# 4_mcu.net
KiCad netlist of a schematic drawn in Altium Designer
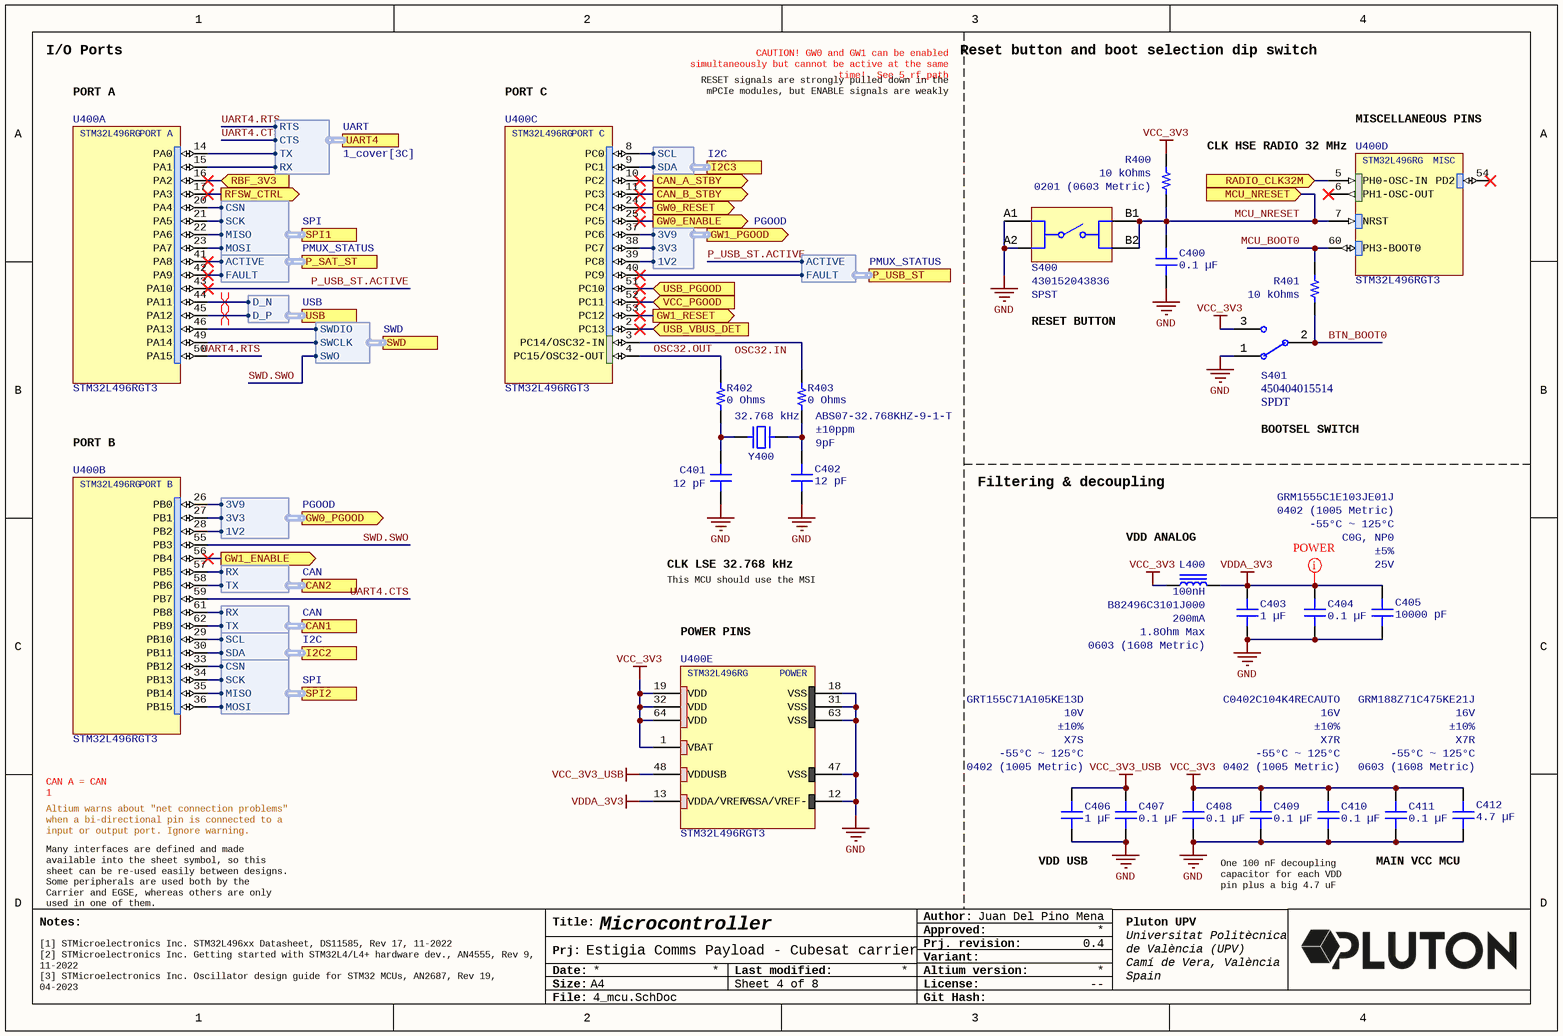
[diagram p0: 4_mcu.SchDoc]

(export (version "E")
  (design (tool "Eeschema 10.0.6"))
  (components
    (comp (ref "C400")
      (value "0.1 µF")
      (footprint "CAP 0402_1005")
      (description "CAP CER 0402 0.1UF 16V X7R 10%")
      (fields (field (name "PART NUMBER") "C0402C104K4RECAUTO") (field (name "MANUFACTURER") "KEMET"))
      (libsource (lib "Celestial Altium Library - altium_library") (part "Capacitor"))
    )
    (comp (ref "C401")
      (value "12 pF")
      (footprint "CAP 0201_0603")
      (description "CAP CER 12PF 25V C0G/NP0 0201")
      (fields (field (name "PART NUMBER") "CBR02C120F3GAC") (field (name "MANUFACTURER") "KEMET"))
      (libsource (lib "Celestial Altium Library - altium_library") (part "Capacitor"))
    )
    (comp (ref "C402")
      (value "12 pF")
      (footprint "CAP 0201_0603")
      (description "CAP CER 12PF 25V C0G/NP0 0201")
      (fields (field (name "PART NUMBER") "CBR02C120F3GAC") (field (name "MANUFACTURER") "KEMET"))
      (libsource (lib "Celestial Altium Library - altium_library") (part "Capacitor"))
    )
    (comp (ref "C403")
      (value "1 µF")
      (footprint "CAP 0402_1005")
      (description "CAP CER 1UF 10V X7S 0402")
      (fields
        (field (name "PART NUMBER") "GRT155C71A105KE13D")
        (field (name "MANUFACTURER") "Murata Electronics")
      )
      (libsource (lib "Celestial Altium Library - altium_library") (part "Capacitor"))
    )
    (comp (ref "C404")
      (value "0.1 µF")
      (footprint "CAP 0402_1005")
      (description "CAP CER 0402 0.1UF 16V X7R 10%")
      (fields (field (name "PART NUMBER") "C0402C104K4RECAUTO") (field (name "MANUFACTURER") "KEMET"))
      (libsource (lib "Celestial Altium Library - altium_library") (part "Capacitor"))
    )
    (comp (ref "C405")
      (value "10000 pF")
      (footprint "CAP 0402_1005")
      (description "CAP CER 10000PF 25V C0G/NP0 0402")
      (fields
        (field (name "PART NUMBER") "GRM1555C1E103JE01J")
        (field (name "DEVICE PACKAGE") "0402 (1005 Metric)")
        (field (name "MANUFACTURER") "Murata Electronics")
        (field (name "OPERATING TEMPERATURE") "-55°C ~ 125°C")
        (field (name "TEMPERATURE COEFFICIENT") "C0G, NP0")
        (field (name "TOLERANCE") "±5%")
        (field (name "VOLTAGE - RATED") "25V")
      )
      (libsource (lib "Celestial Altium Library - altium_library") (part "Capacitor"))
    )
    (comp (ref "C406")
      (value "1 µF")
      (footprint "CAP 0402_1005")
      (description "CAP CER 1UF 10V X7S 0402")
      (fields
        (field (name "PART NUMBER") "GRT155C71A105KE13D")
        (field (name "DEVICE PACKAGE") "0402 (1005 Metric)")
        (field (name "MANUFACTURER") "Murata Electronics")
        (field (name "OPERATING TEMPERATURE") "-55°C ~ 125°C")
        (field (name "TEMPERATURE COEFFICIENT") "X7S")
        (field (name "TOLERANCE") "±10%")
        (field (name "VOLTAGE - RATED") "10V")
      )
      (libsource (lib "Celestial Altium Library - altium_library") (part "Capacitor"))
    )
    (comp (ref "C407")
      (value "0.1 µF")
      (footprint "CAP 0402_1005")
      (description "CAP CER 0402 0.1UF 16V X7R 10%")
      (fields (field (name "PART NUMBER") "C0402C104K4RECAUTO") (field (name "MANUFACTURER") "KEMET"))
      (libsource (lib "Celestial Altium Library - altium_library") (part "Capacitor"))
    )
    (comp (ref "C408")
      (value "0.1 µF")
      (footprint "CAP 0402_1005")
      (description "CAP CER 0402 0.1UF 16V X7R 10%")
      (fields (field (name "PART NUMBER") "C0402C104K4RECAUTO") (field (name "MANUFACTURER") "KEMET"))
      (libsource (lib "Celestial Altium Library - altium_library") (part "Capacitor"))
    )
    (comp (ref "C409")
      (value "0.1 µF")
      (footprint "CAP 0402_1005")
      (description "CAP CER 0402 0.1UF 16V X7R 10%")
      (fields
        (field (name "PART NUMBER") "C0402C104K4RECAUTO")
        (field (name "MANUFACTURER") "KEMET")
        (field (name "OPERATING TEMPERATURE") "-55°C ~ 125°C")
        (field (name "PACKAGE / CASE") "0402 (1005 Metric)")
        (field (name "TEMPERATURE COEFFICIENT") "X7R")
        (field (name "TOLERANCE") "±10%")
        (field (name "VOLTAGE - RATED") "16V")
      )
      (libsource (lib "Celestial Altium Library - altium_library") (part "Capacitor"))
    )
    (comp (ref "C410")
      (value "0.1 µF")
      (footprint "CAP 0402_1005")
      (description "CAP CER 0402 0.1UF 16V X7R 10%")
      (fields (field (name "PART NUMBER") "C0402C104K4RECAUTO") (field (name "MANUFACTURER") "KEMET"))
      (libsource (lib "Celestial Altium Library - altium_library") (part "Capacitor"))
    )
    (comp (ref "C411")
      (value "0.1 µF")
      (footprint "CAP 0402_1005")
      (description "CAP CER 0402 0.1UF 16V X7R 10%")
      (fields (field (name "PART NUMBER") "C0402C104K4RECAUTO") (field (name "MANUFACTURER") "KEMET"))
      (libsource (lib "Celestial Altium Library - altium_library") (part "Capacitor"))
    )
    (comp (ref "C412")
      (value "4.7 µF")
      (footprint "CAP 0603_1608")
      (description "CAP CER 4.7UF 16V X7R 0603")
      (fields
        (field (name "PART NUMBER") "GRM188Z71C475KE21J")
        (field (name "DEVICE PACKAGE") "0603 (1608 Metric)")
        (field (name "MANUFACTURER") "Murata Electronics")
        (field (name "OPERATING TEMPERATURE") "-55°C ~ 125°C")
        (field (name "TEMPERATURE COEFFICIENT") "X7R")
        (field (name "TOLERANCE") "±10%")
        (field (name "VOLTAGE - RATED") "16V")
      )
      (libsource (lib "Celestial Altium Library - altium_library") (part "Capacitor"))
    )
    (comp (ref "L400")
      (value "100nH")
      (footprint "IND 0603_1608 RF WW")
      (description "FIXED IND 100NH 200MA 1.8 OHM")
      (fields
        (field (name "PART NUMBER") "B82496C3101J000")
        (field (name "CURRENT RATING (AMPS)") "200mA")
        (field (name "DC RESISTANCE (DCR)") "1.8Ohm Max")
        (field (name "DEVICE PACKAGE") "0603 (1608 Metric)")
        (field (name "MANUFACTURER") "TDK Electronics Inc.")
        (field (name "TOLERANCE") "±5%")
      )
      (libsource (lib "Celestial Altium Library - altium_library") (part "Inductor"))
    )
    (comp (ref "R400")
      (value "10 kOhms")
      (footprint "RES 0201_0603")
      (description "RES SMD 10K OHM 1% 1/20W 0201")
      (fields
        (field (name "PART NUMBER") "AF0201FR-0710KL")
        (field (name "MANUFACTURER") "Yageo")
        (field (name "PACKAGE / CASE") "0201 (0603 Metric)")
      )
      (libsource (lib "Celestial Altium Library - altium_library") (part "Resistor"))
    )
    (comp (ref "R401")
      (value "10 kOhms")
      (footprint "RES 0201_0603")
      (description "RES SMD 10K OHM 1% 1/20W 0201")
      (fields (field (name "PART NUMBER") "AF0201FR-0710KL") (field (name "MANUFACTURER") "Yageo"))
      (libsource (lib "Celestial Altium Library - altium_library") (part "Resistor"))
    )
    (comp (ref "R402")
      (value "0 Ohms")
      (footprint "RES 0201_0603")
      (description "RES SMD 0 OHM JUMPER 1/20W 0201")
      (fields (field (name "PART NUMBER") "AC0201JR-070RL") (field (name "MANUFACTURER") "Yageo"))
      (libsource (lib "Celestial Altium Library - altium_library") (part "Resistor"))
    )
    (comp (ref "R403")
      (value "0 Ohms")
      (footprint "RES 0201_0603")
      (description "RES SMD 0 OHM JUMPER 1/20W 0201")
      (fields (field (name "PART NUMBER") "AC0201JR-070RL") (field (name "MANUFACTURER") "Yageo"))
      (libsource (lib "Celestial Altium Library - altium_library") (part "Resistor"))
    )
    (comp (ref "S400")
      (value "430152043836")
      (footprint "WS-TASV_L6W6H4.3_4301x20438x6")
      (fields (field (name "THROW CONFIGURATION") "SPST"))
      (libsource (lib "Altium Content Vault") (part "SPST-NO_4P"))
    )
    (comp (ref "S401")
      (value "450404015514")
      (footprint "WURTH WS-SLSU 450404015514")
      (description "MINI SLIDE SWITCH 6.7 X 2.7 MM.")
      (fields
        (field (name "PART NUMBER") "450404015514")
        (field (name "CIRCUIT") "SPDT")
        (field (name "MANUFACTURER") "Würth Elektronik")
        (field (name "PUBLISHER") "Wurth Elektronik")
      )
      (libsource (lib "Celestial Altium Library - altium_library") (part "WURTH WS-SLSU 450404015514"))
    )
    (comp (ref "U400")
      (value "STM32L496RGT3")
      (footprint "ics:LQFP64")
      (libsource (lib "stm32") (part "STM32L496RGT3"))
    )
    (comp (ref "Y400")
      (value "32.768 kHz")
      (footprint "ABRACON ABS07")
      (description "CRYSTAL 32.7680KHZ 9PF SMD")
      (fields
        (field (name "PART NUMBER") "ABS07-32.768KHZ-9-1-T")
        (field (name "FREQUENCY") "32.768 kHz")
        (field (name "FREQUENCY TOLERANCE") "±10ppm")
        (field (name "LOAD CAPACITANCE") "9pF")
        (field (name "MANUFACTURER") "Abracon LLC")
      )
      (libsource (lib "Celestial Altium Library - altium_library") (part "Abracon Crystal ABS07"))
    )
  )
  (nets
    (net (code "9") (name "/BTN_BOOT0") (class "Default")
      (node (ref "R401") (pin "1") (pinfunction "1_1") (pintype "passive"))
      (node (ref "S401") (pin "2") (pinfunction "COM_2") (pintype "passive"))
    )
    (net (code "10") (name "/CAN_A_STBY") (class "Default")
      (node (ref "U400") (pin "10") (pinfunction "PC2_10") (pintype "bidirectional+no_connect"))
    )
    (net (code "11") (name "/CAN_B_STBY") (class "Default")
      (node (ref "U400") (pin "11") (pinfunction "PC3_11") (pintype "bidirectional+no_connect"))
    )
    (net (code "12") (name "/D_N") (class "Default")
      (node (ref "U400") (pin "44") (pinfunction "PA11_44") (pintype "bidirectional"))
    )
    (net (code "13") (name "/D_P") (class "Default")
      (node (ref "U400") (pin "45") (pinfunction "PA12_45") (pintype "bidirectional"))
    )
    (net (code "14") (name "/GW0_ENABLE") (class "Default")
      (node (ref "U400") (pin "25") (pinfunction "PC5_25") (pintype "bidirectional+no_connect"))
    )
    (net (code "15") (name "/GW0_RESET") (class "Default")
      (node (ref "U400") (pin "24") (pinfunction "PC4_24") (pintype "bidirectional+no_connect"))
    )
    (net (code "16") (name "/GW1_ENABLE") (class "Default")
      (node (ref "U400") (pin "56") (pinfunction "PB4_56") (pintype "bidirectional+no_connect"))
    )
    (net (code "17") (name "/GW1_RESET") (class "Default")
      (node (ref "U400") (pin "53") (pinfunction "PC12_53") (pintype "bidirectional+no_connect"))
    )
    (net (code "19") (name "/MCU_BOOT0") (class "Default")
      (node (ref "R401") (pin "2") (pinfunction "2_2") (pintype "passive"))
      (node (ref "U400") (pin "60") (pinfunction "PH3-BOOT0_60") (pintype "bidirectional"))
    )
    (net (code "20") (name "/MCU_NRESET") (class "Default")
      (node (ref "C400") (pin "2") (pinfunction "2_2") (pintype "passive"))
      (node (ref "R400") (pin "1") (pinfunction "1_1") (pintype "passive"))
      (node (ref "S400") (pin "B1") (pinfunction "B1_B1") (pintype "passive"))
      (node (ref "S400") (pin "B2") (pinfunction "B2_B2") (pintype "passive"))
      (node (ref "U400") (pin "7") (pinfunction "NRST_7") (pintype "input"))
    )
    (net (code "21") (name "/OSC32.IN") (class "Default")
      (node (ref "R403") (pin "2") (pinfunction "2_2") (pintype "passive"))
      (node (ref "U400") (pin "3") (pinfunction "PC14/OSC32-IN_3") (pintype "bidirectional"))
    )
    (net (code "22") (name "/OSC32.OUT") (class "Default")
      (node (ref "R402") (pin "2") (pinfunction "2_2") (pintype "passive"))
      (node (ref "U400") (pin "4") (pinfunction "PC15/OSC32-OUT_4") (pintype "bidirectional"))
    )
    (net (code "23") (name "/P_USB_ST.ACTIVE") (class "Default")
      (node (ref "U400") (pin "43") (pinfunction "PA10_43") (pintype "bidirectional+no_connect"))
    )
    (net (code "24") (name "/RADIO_CLK32M") (class "Default")
      (node (ref "U400") (pin "5") (pinfunction "PH0-OSC-IN_5") (pintype "input"))
    )
    (net (code "25") (name "/RBF_3V3") (class "Default")
      (node (ref "U400") (pin "16") (pinfunction "PA2_16") (pintype "bidirectional+no_connect"))
    )
    (net (code "26") (name "/RFSW_CTRL") (class "Default")
      (node (ref "U400") (pin "17") (pinfunction "PA3_17") (pintype "bidirectional+no_connect"))
    )
    (net (code "27") (name "/SWCLK") (class "Default")
      (node (ref "U400") (pin "49") (pinfunction "PA14_49") (pintype "bidirectional"))
    )
    (net (code "28") (name "/SWD.SWO") (class "Default")
      (node (ref "U400") (pin "55") (pinfunction "PB3_55") (pintype "bidirectional"))
    )
    (net (code "29") (name "/SWDIO") (class "Default")
      (node (ref "U400") (pin "46") (pinfunction "PA13_46") (pintype "bidirectional"))
    )
    (net (code "30") (name "/UART4.CTS") (class "Default")
      (node (ref "U400") (pin "59") (pinfunction "PB7_59") (pintype "bidirectional"))
    )
    (net (code "31") (name "/UART4.RTS") (class "Default")
      (node (ref "U400") (pin "50") (pinfunction "PA15_50") (pintype "bidirectional"))
    )
    (net (code "32") (name "/USB_PGOOD") (class "Default")
      (node (ref "U400") (pin "51") (pinfunction "PC10_51") (pintype "bidirectional+no_connect"))
    )
    (net (code "33") (name "/USB_VBUS_DET") (class "Default")
      (node (ref "U400") (pin "2") (pinfunction "PC13_2") (pintype "bidirectional+no_connect"))
    )
    (net (code "34") (name "/VCC_PGOOD") (class "Default")
      (node (ref "U400") (pin "52") (pinfunction "PC11_52") (pintype "bidirectional+no_connect"))
    )
    (net (code "42") (name "GND") (class "Default")
      (node (ref "C400") (pin "1") (pinfunction "1_1") (pintype "passive"))
      (node (ref "C401") (pin "1") (pinfunction "1_1") (pintype "passive"))
      (node (ref "C402") (pin "1") (pinfunction "1_1") (pintype "passive"))
      (node (ref "C403") (pin "1") (pinfunction "1_1") (pintype "passive"))
      (node (ref "C404") (pin "1") (pinfunction "1_1") (pintype "passive"))
      (node (ref "C405") (pin "1") (pinfunction "1_1") (pintype "passive"))
      (node (ref "C406") (pin "1") (pinfunction "1_1") (pintype "passive"))
      (node (ref "C407") (pin "1") (pinfunction "1_1") (pintype "passive"))
      (node (ref "C408") (pin "1") (pinfunction "1_1") (pintype "passive"))
      (node (ref "C409") (pin "1") (pinfunction "1_1") (pintype "passive"))
      (node (ref "C410") (pin "1") (pinfunction "1_1") (pintype "passive"))
      (node (ref "C411") (pin "1") (pinfunction "1_1") (pintype "passive"))
      (node (ref "C412") (pin "1") (pinfunction "1_1") (pintype "passive"))
      (node (ref "S400") (pin "A1") (pinfunction "A1_A1") (pintype "passive"))
      (node (ref "S400") (pin "A2") (pinfunction "A2_A2") (pintype "passive"))
      (node (ref "S401") (pin "1") (pinfunction "1_1") (pintype "passive"))
      (node (ref "U400") (pin "12") (pinfunction "VSSA/VREF-_12") (pintype "power_in"))
      (node (ref "U400") (pin "18") (pinfunction "VSS_18") (pintype "power_in"))
      (node (ref "U400") (pin "31") (pinfunction "VSS_31") (pintype "power_in"))
      (node (ref "U400") (pin "47") (pinfunction "VSS_47") (pintype "power_in"))
      (node (ref "U400") (pin "63") (pinfunction "VSS_63") (pintype "power_in"))
    )
    (net (code "43") (name "Net-(C401-Pad2)") (class "Default")
      (node (ref "C401") (pin "2") (pinfunction "2_2") (pintype "passive"))
      (node (ref "R402") (pin "1") (pinfunction "1_1") (pintype "passive"))
      (node (ref "Y400") (pin "1") (pinfunction "1_1") (pintype "passive"))
    )
    (net (code "44") (name "Net-(C402-Pad2)") (class "Default")
      (node (ref "C402") (pin "2") (pinfunction "2_2") (pintype "passive"))
      (node (ref "R403") (pin "1") (pinfunction "1_1") (pintype "passive"))
      (node (ref "Y400") (pin "2") (pinfunction "2_2") (pintype "passive"))
    )
    (net (code "45") (name "VCC_3V3") (class "Default")
      (node (ref "C408") (pin "2") (pinfunction "2_2") (pintype "passive"))
      (node (ref "C409") (pin "2") (pinfunction "2_2") (pintype "passive"))
      (node (ref "C410") (pin "2") (pinfunction "2_2") (pintype "passive"))
      (node (ref "C411") (pin "2") (pinfunction "2_2") (pintype "passive"))
      (node (ref "C412") (pin "2") (pinfunction "2_2") (pintype "passive"))
      (node (ref "L400") (pin "1") (pinfunction "1_1") (pintype "passive"))
      (node (ref "R400") (pin "2") (pinfunction "2_2") (pintype "passive"))
      (node (ref "S401") (pin "3") (pinfunction "3_3") (pintype "passive"))
      (node (ref "U400") (pin "1") (pinfunction "VBAT_1") (pintype "power_in"))
      (node (ref "U400") (pin "19") (pinfunction "VDD_19") (pintype "power_in"))
      (node (ref "U400") (pin "32") (pinfunction "VDD_32") (pintype "power_in"))
      (node (ref "U400") (pin "64") (pinfunction "VDD_64") (pintype "power_in"))
    )
    (net (code "46") (name "VCC_3V3_USB") (class "Default")
      (node (ref "C406") (pin "2") (pinfunction "2_2") (pintype "passive"))
      (node (ref "C407") (pin "2") (pinfunction "2_2") (pintype "passive"))
      (node (ref "U400") (pin "48") (pinfunction "VDDUSB_48") (pintype "power_in"))
    )
    (net (code "47") (name "VDDA_3V3") (class "Default")
      (node (ref "C403") (pin "2") (pinfunction "2_2") (pintype "passive"))
      (node (ref "C404") (pin "2") (pinfunction "2_2") (pintype "passive"))
      (node (ref "C405") (pin "2") (pinfunction "2_2") (pintype "passive"))
      (node (ref "L400") (pin "2") (pinfunction "2_2") (pintype "passive"))
      (node (ref "U400") (pin "13") (pinfunction "VDDA/VREF+_13") (pintype "power_in"))
    )
    (net (code "48") (name "unconnected-(U400A-PA0-Pad14)") (class "Default")
      (node (ref "U400") (pin "14") (pinfunction "PA0_14") (pintype "bidirectional"))
    )
    (net (code "49") (name "unconnected-(U400A-PA1-Pad15)") (class "Default")
      (node (ref "U400") (pin "15") (pinfunction "PA1_15") (pintype "bidirectional"))
    )
    (net (code "50") (name "unconnected-(U400A-PA4-Pad20)") (class "Default")
      (node (ref "U400") (pin "20") (pinfunction "PA4_20") (pintype "bidirectional"))
    )
    (net (code "51") (name "unconnected-(U400A-PA5-Pad21)") (class "Default")
      (node (ref "U400") (pin "21") (pinfunction "PA5_21") (pintype "bidirectional"))
    )
    (net (code "52") (name "unconnected-(U400A-PA6-Pad22)") (class "Default")
      (node (ref "U400") (pin "22") (pinfunction "PA6_22") (pintype "bidirectional"))
    )
    (net (code "53") (name "unconnected-(U400A-PA7-Pad23)") (class "Default")
      (node (ref "U400") (pin "23") (pinfunction "PA7_23") (pintype "bidirectional"))
    )
    (net (code "54") (name "unconnected-(U400A-PA8-Pad41)") (class "Default")
      (node (ref "U400") (pin "41") (pinfunction "PA8_41") (pintype "bidirectional+no_connect"))
    )
    (net (code "55") (name "unconnected-(U400A-PA9-Pad42)") (class "Default")
      (node (ref "U400") (pin "42") (pinfunction "PA9_42") (pintype "bidirectional+no_connect"))
    )
    (net (code "56") (name "unconnected-(U400B-PB0-Pad26)") (class "Default")
      (node (ref "U400") (pin "26") (pinfunction "PB0_26") (pintype "bidirectional"))
    )
    (net (code "57") (name "unconnected-(U400B-PB1-Pad27)") (class "Default")
      (node (ref "U400") (pin "27") (pinfunction "PB1_27") (pintype "bidirectional"))
    )
    (net (code "58") (name "unconnected-(U400B-PB2-Pad28)") (class "Default")
      (node (ref "U400") (pin "28") (pinfunction "PB2_28") (pintype "bidirectional"))
    )
    (net (code "59") (name "unconnected-(U400B-PB5-Pad57)") (class "Default")
      (node (ref "U400") (pin "57") (pinfunction "PB5_57") (pintype "bidirectional"))
    )
    (net (code "60") (name "unconnected-(U400B-PB6-Pad58)") (class "Default")
      (node (ref "U400") (pin "58") (pinfunction "PB6_58") (pintype "bidirectional"))
    )
    (net (code "61") (name "unconnected-(U400B-PB8-Pad61)") (class "Default")
      (node (ref "U400") (pin "61") (pinfunction "PB8_61") (pintype "bidirectional"))
    )
    (net (code "62") (name "unconnected-(U400B-PB9-Pad62)") (class "Default")
      (node (ref "U400") (pin "62") (pinfunction "PB9_62") (pintype "bidirectional"))
    )
    (net (code "63") (name "unconnected-(U400B-PB10-Pad29)") (class "Default")
      (node (ref "U400") (pin "29") (pinfunction "PB10_29") (pintype "bidirectional"))
    )
    (net (code "64") (name "unconnected-(U400B-PB11-Pad30)") (class "Default")
      (node (ref "U400") (pin "30") (pinfunction "PB11_30") (pintype "bidirectional"))
    )
    (net (code "65") (name "unconnected-(U400B-PB12-Pad33)") (class "Default")
      (node (ref "U400") (pin "33") (pinfunction "PB12_33") (pintype "bidirectional"))
    )
    (net (code "66") (name "unconnected-(U400B-PB13-Pad34)") (class "Default")
      (node (ref "U400") (pin "34") (pinfunction "PB13_34") (pintype "bidirectional"))
    )
    (net (code "67") (name "unconnected-(U400B-PB14-Pad35)") (class "Default")
      (node (ref "U400") (pin "35") (pinfunction "PB14_35") (pintype "bidirectional"))
    )
    (net (code "68") (name "unconnected-(U400B-PB15-Pad36)") (class "Default")
      (node (ref "U400") (pin "36") (pinfunction "PB15_36") (pintype "bidirectional"))
    )
    (net (code "69") (name "unconnected-(U400C-PC0-Pad8)") (class "Default")
      (node (ref "U400") (pin "8") (pinfunction "PC0_8") (pintype "bidirectional"))
    )
    (net (code "70") (name "unconnected-(U400C-PC1-Pad9)") (class "Default")
      (node (ref "U400") (pin "9") (pinfunction "PC1_9") (pintype "bidirectional"))
    )
    (net (code "71") (name "unconnected-(U400C-PC6-Pad37)") (class "Default")
      (node (ref "U400") (pin "37") (pinfunction "PC6_37") (pintype "bidirectional"))
    )
    (net (code "72") (name "unconnected-(U400C-PC7-Pad38)") (class "Default")
      (node (ref "U400") (pin "38") (pinfunction "PC7_38") (pintype "bidirectional"))
    )
    (net (code "73") (name "unconnected-(U400C-PC8-Pad39)") (class "Default")
      (node (ref "U400") (pin "39") (pinfunction "PC8_39") (pintype "bidirectional"))
    )
    (net (code "74") (name "unconnected-(U400C-PC9-Pad40)") (class "Default")
      (node (ref "U400") (pin "40") (pinfunction "PC9_40") (pintype "bidirectional+no_connect"))
    )
    (net (code "75") (name "unconnected-(U400D-PD2-Pad54)") (class "Default")
      (node (ref "U400") (pin "54") (pinfunction "PD2_54") (pintype "bidirectional+no_connect"))
    )
    (net (code "76") (name "unconnected-(U400D-PH1-OSC-OUT-Pad6)") (class "Default")
      (node (ref "U400") (pin "6") (pinfunction "PH1-OSC-OUT_6") (pintype "output+no_connect"))
    )
  )
)
